# motor_line.net
KiCad netlist of a schematic drawn in EAGLE
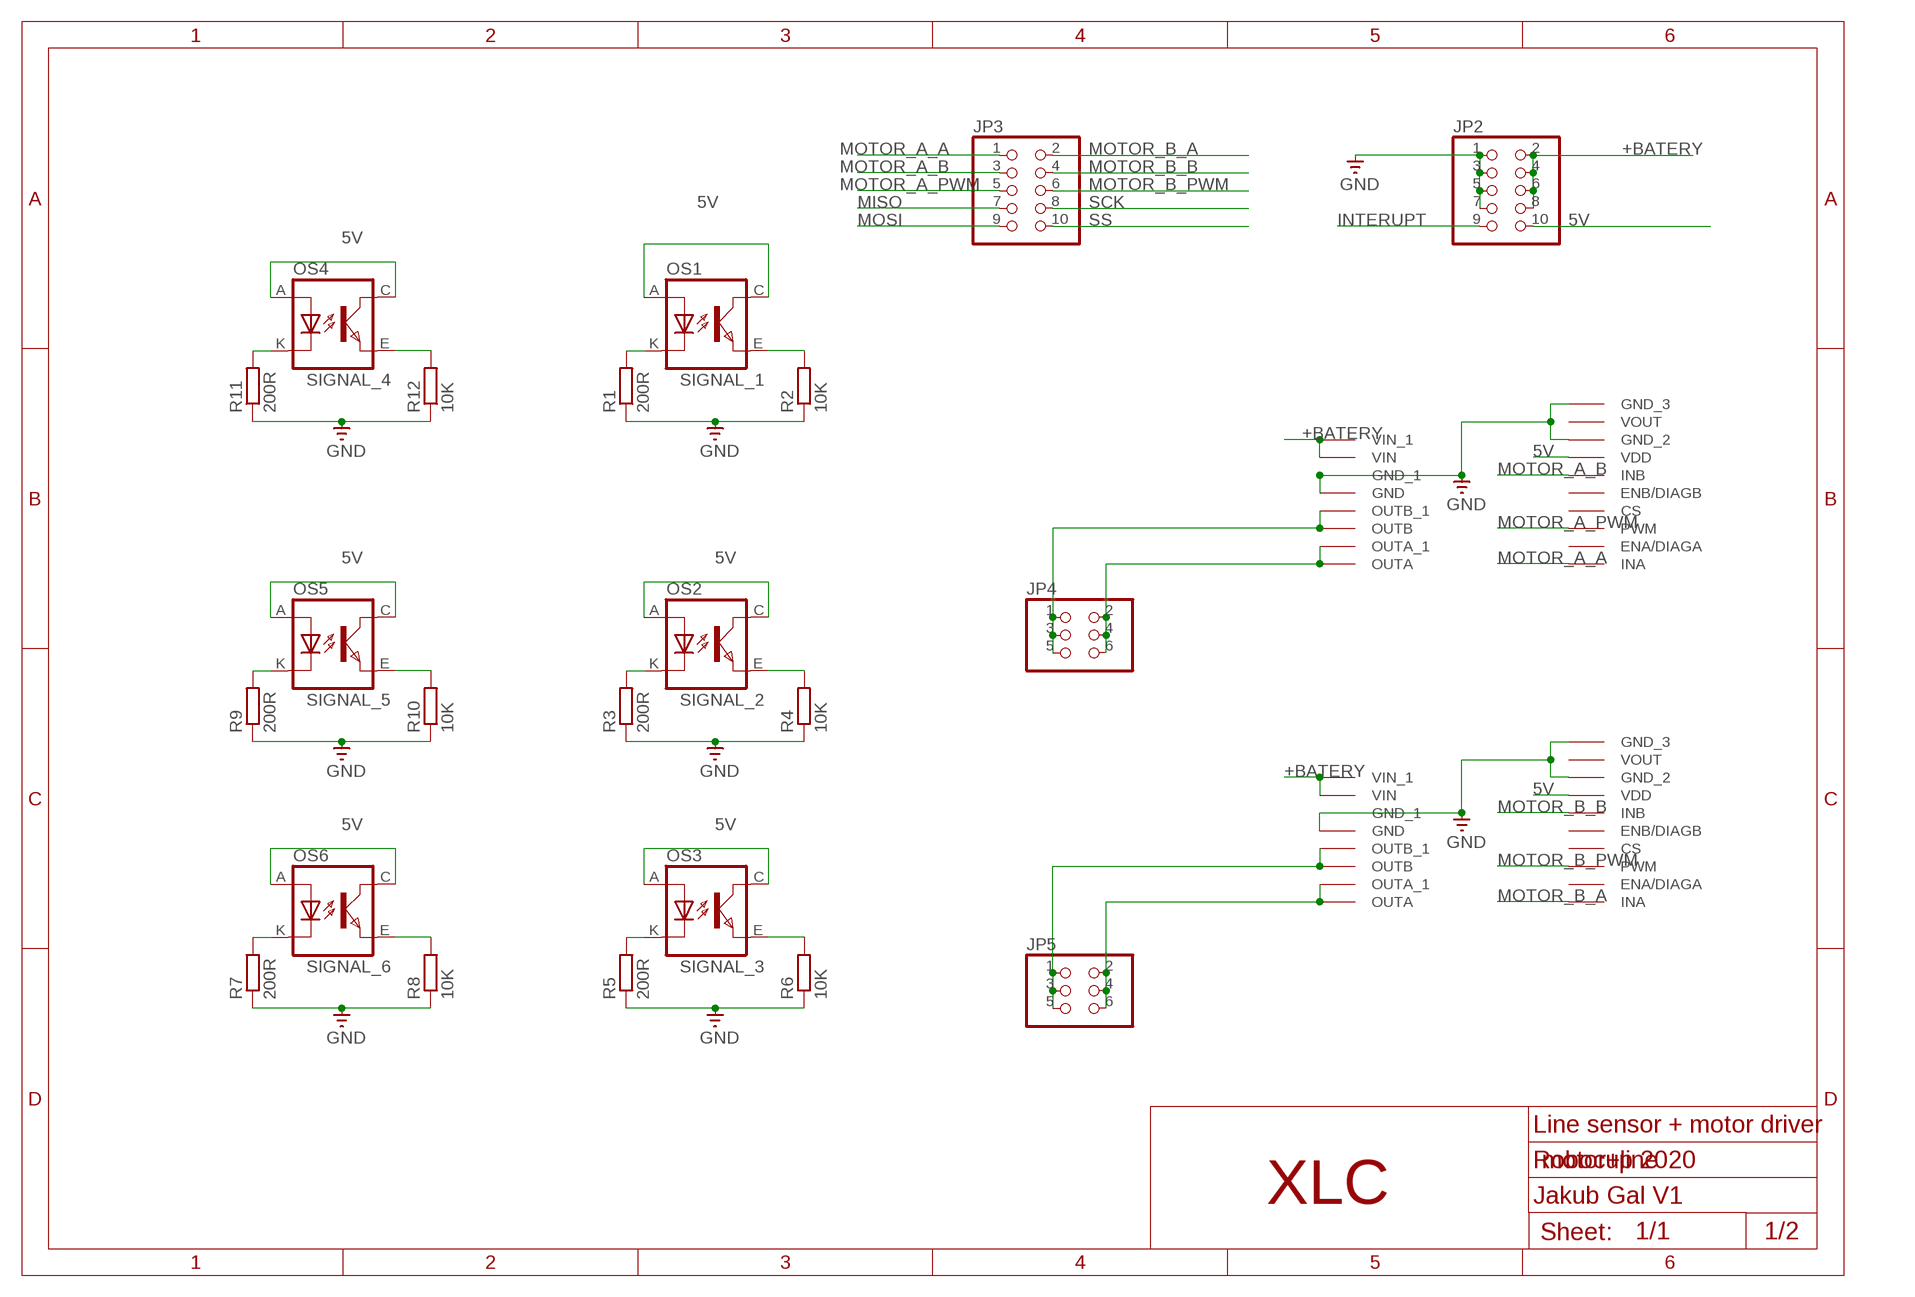
[diagram p0: schematic, sheet 1, part 1 of 2]
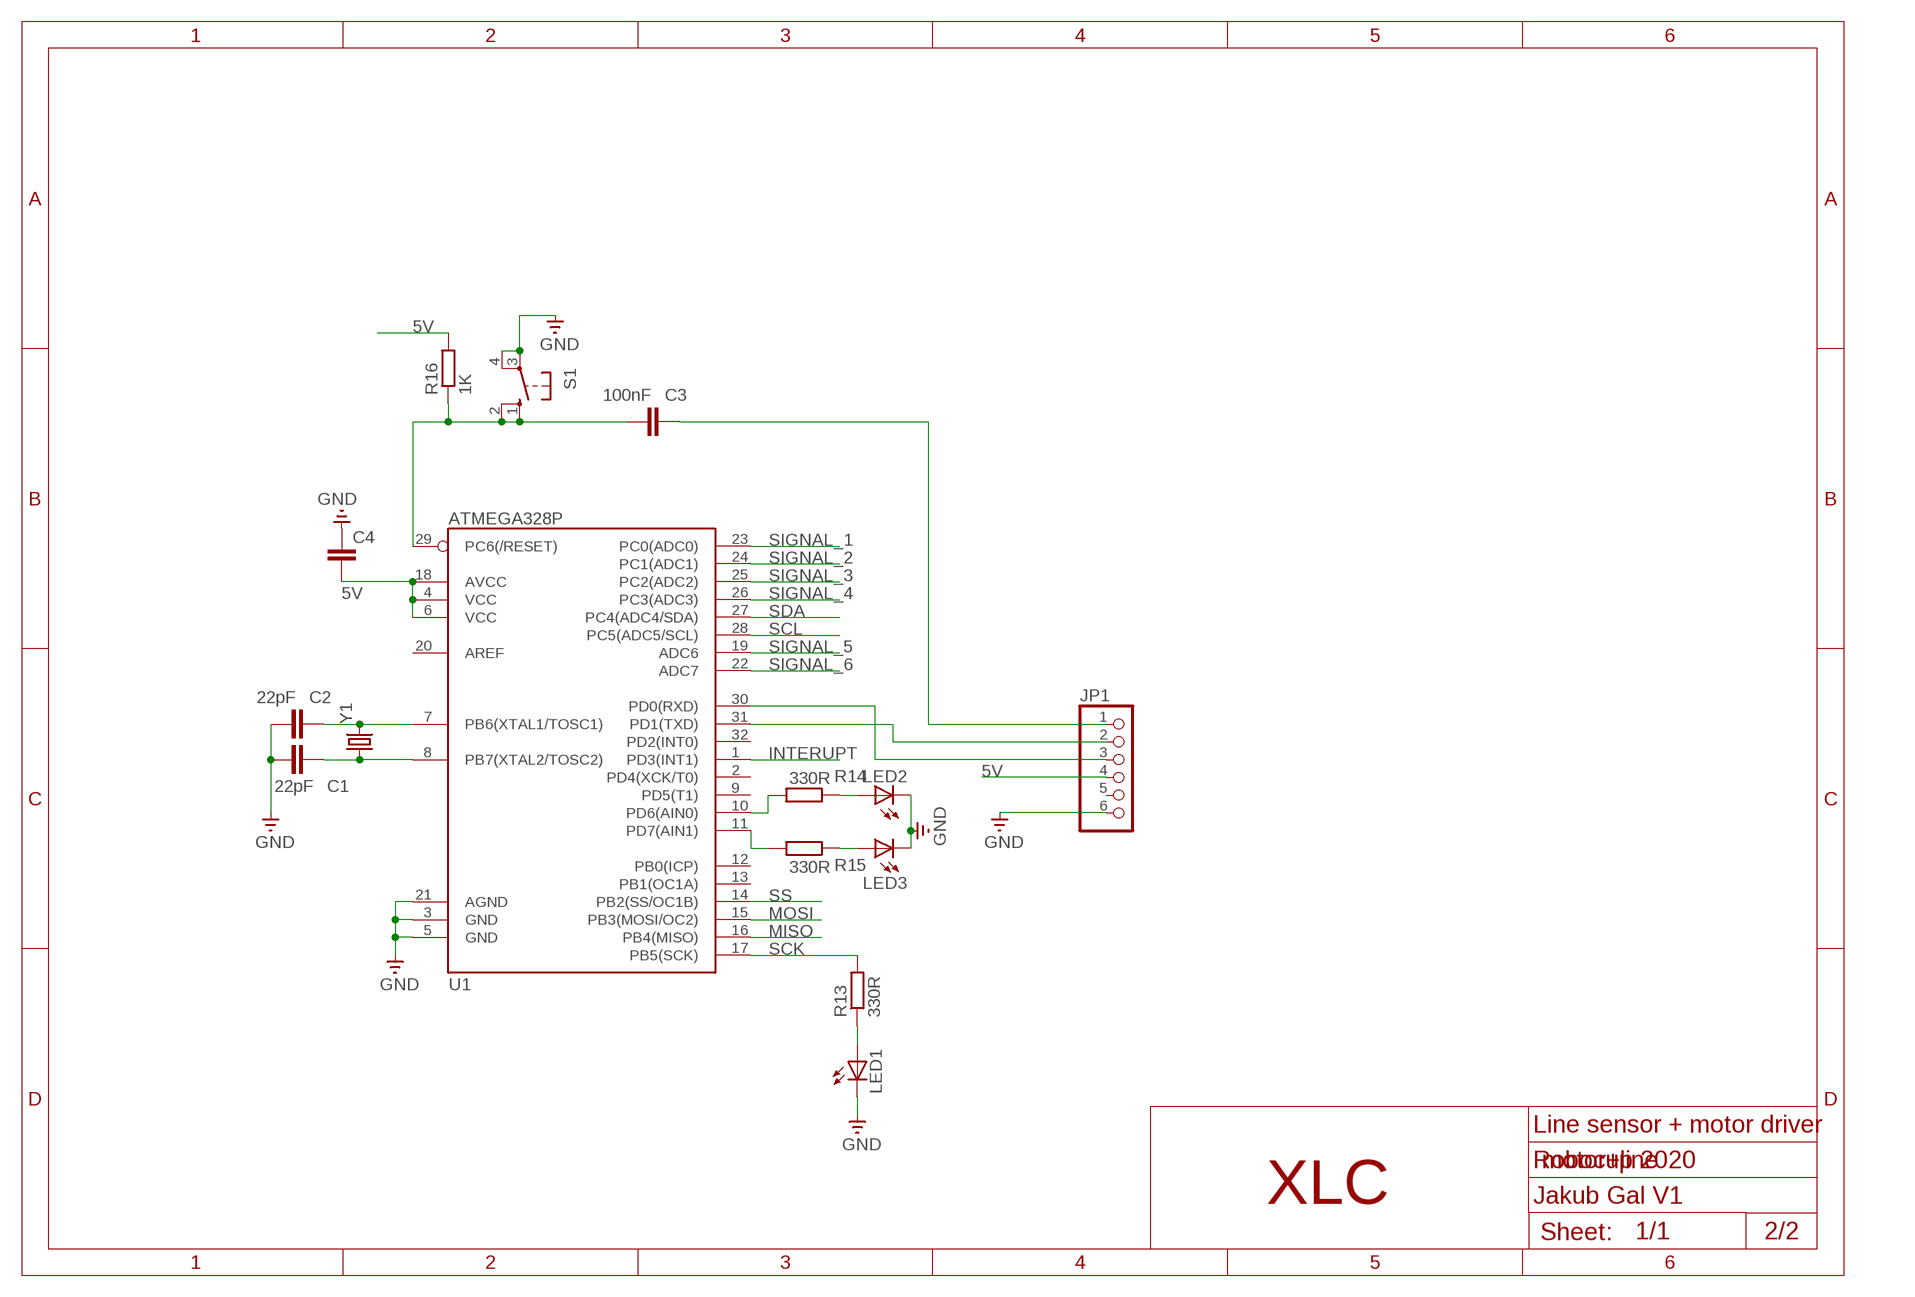
[diagram p1: schematic, sheet 1, part 2 of 2]

(export (version "E")
  (design (tool "Eeschema 10.0.6"))
  (components
    (comp (ref "C1")
      (value "22pF")
      (footprint "eagle-import:C0603")
      (libsource (lib "eagle-import") (part "C-EUC0603"))
    )
    (comp (ref "C2")
      (value "22pF")
      (footprint "eagle-import:C0603")
      (libsource (lib "eagle-import") (part "C-EUC0603"))
    )
    (comp (ref "C3")
      (value "100nF")
      (footprint "eagle-import:C0603")
      (libsource (lib "eagle-import") (part "C-EUC0603"))
    )
    (comp (ref "C4")
      (value "C-EUC0603")
      (footprint "eagle-import:C0603")
      (libsource (lib "eagle-import") (part "rcl_334_C-EUC0603"))
    )
    (comp (ref "JP1")
      (value "PINHD-1X6/90")
      (footprint "eagle-import:1X06_90")
      (libsource (lib "eagle-import") (part "PINHD-1X6/90"))
    )
    (comp (ref "JP2")
      (value "PINHD-2X5")
      (footprint "eagle-import:2X05")
      (libsource (lib "eagle-import") (part "PINHD-2X5"))
    )
    (comp (ref "JP3")
      (value "PINHD-2X5")
      (footprint "eagle-import:2X05")
      (libsource (lib "eagle-import") (part "PINHD-2X5"))
    )
    (comp (ref "JP4")
      (value "PINHD-2X3")
      (footprint "eagle-import:2X03")
      (libsource (lib "eagle-import") (part "PINHD-2X3"))
    )
    (comp (ref "JP5")
      (value "PINHD-2X3")
      (footprint "eagle-import:2X03")
      (libsource (lib "eagle-import") (part "PINHD-2X3"))
    )
    (comp (ref "LED1")
      (value "LEDCHIPLED_0603")
      (footprint "eagle-import:CHIPLED_0603")
      (libsource (lib "eagle-import") (part "LEDCHIPLED_0603"))
    )
    (comp (ref "LED2")
      (value "LEDCHIPLED_0603")
      (footprint "eagle-import:CHIPLED_0603")
      (libsource (lib "eagle-import") (part "LEDCHIPLED_0603"))
    )
    (comp (ref "LED3")
      (value "LEDCHIPLED_0603")
      (footprint "eagle-import:CHIPLED_0603")
      (libsource (lib "eagle-import") (part "LEDCHIPLED_0603"))
    )
    (comp (ref "OS1")
      (value "TCRT5000")
      (footprint "eagle-import:TCRT5000")
      (libsource (lib "eagle-import") (part "TCRT5000"))
    )
    (comp (ref "OS2")
      (value "TCRT5000")
      (footprint "eagle-import:TCRT5000")
      (libsource (lib "eagle-import") (part "TCRT5000"))
    )
    (comp (ref "OS3")
      (value "TCRT5000")
      (footprint "eagle-import:TCRT5000")
      (libsource (lib "eagle-import") (part "TCRT5000"))
    )
    (comp (ref "OS4")
      (value "TCRT5000")
      (footprint "eagle-import:TCRT5000")
      (fields (field (name "SPICEPREFIX") "O"))
      (libsource (lib "eagle-import") (part "TCRT5000"))
    )
    (comp (ref "OS5")
      (value "TCRT5000")
      (footprint "eagle-import:TCRT5000")
      (libsource (lib "eagle-import") (part "TCRT5000"))
    )
    (comp (ref "OS6")
      (value "TCRT5000")
      (footprint "eagle-import:TCRT5000")
      (fields (field (name "SPICEPREFIX") "O"))
      (libsource (lib "eagle-import") (part "TCRT5000"))
    )
    (comp (ref "R1")
      (value "200R")
      (footprint "eagle-import:R0603")
      (libsource (lib "eagle-import") (part "R-EU_R0603"))
    )
    (comp (ref "R2")
      (value "10K")
      (footprint "eagle-import:R0603")
      (libsource (lib "eagle-import") (part "R-EU_R0603"))
    )
    (comp (ref "R3")
      (value "200R")
      (footprint "eagle-import:R0603")
      (libsource (lib "eagle-import") (part "R-EU_R0603"))
    )
    (comp (ref "R4")
      (value "10K")
      (footprint "eagle-import:R0603")
      (libsource (lib "eagle-import") (part "R-EU_R0603"))
    )
    (comp (ref "R5")
      (value "200R")
      (footprint "eagle-import:R0603")
      (libsource (lib "eagle-import") (part "R-EU_R0603"))
    )
    (comp (ref "R6")
      (value "10K")
      (footprint "eagle-import:R0603")
      (libsource (lib "eagle-import") (part "R-EU_R0603"))
    )
    (comp (ref "R7")
      (value "200R")
      (footprint "eagle-import:R0603")
      (libsource (lib "eagle-import") (part "R-EU_R0603"))
    )
    (comp (ref "R8")
      (value "10K")
      (footprint "eagle-import:R0603")
      (libsource (lib "eagle-import") (part "R-EU_R0603"))
    )
    (comp (ref "R9")
      (value "200R")
      (footprint "eagle-import:R0603")
      (libsource (lib "eagle-import") (part "R-EU_R0603"))
    )
    (comp (ref "R10")
      (value "10K")
      (footprint "eagle-import:R0603")
      (libsource (lib "eagle-import") (part "R-EU_R0603"))
    )
    (comp (ref "R11")
      (value "200R")
      (footprint "eagle-import:R0603")
      (libsource (lib "eagle-import") (part "R-EU_R0603"))
    )
    (comp (ref "R12")
      (value "10K")
      (footprint "eagle-import:R0603")
      (libsource (lib "eagle-import") (part "R-EU_R0603"))
    )
    (comp (ref "R13")
      (value "330R")
      (footprint "eagle-import:R0603")
      (libsource (lib "eagle-import") (part "R-EU_R0603"))
    )
    (comp (ref "R14")
      (value "330R")
      (footprint "eagle-import:R0603")
      (libsource (lib "eagle-import") (part "R-EU_R0603"))
    )
    (comp (ref "R15")
      (value "330R")
      (footprint "eagle-import:R0603")
      (libsource (lib "eagle-import") (part "R-EU_R0603"))
    )
    (comp (ref "R16")
      (value "1K")
      (footprint "eagle-import:R0603")
      (libsource (lib "eagle-import") (part "R-EU_R0603"))
    )
    (comp (ref "S1")
      (value "10-XX")
      (footprint "eagle-import:B3F-10XX")
      (fields (field (name "MPN") "B3F-1000"))
      (libsource (lib "eagle-import") (part "10-XX"))
    )
    (comp (ref "U$1")
      (value "MOTOR_DRIVER")
      (footprint "eagle-import:MOTOR_DRIVER")
      (libsource (lib "eagle-import") (part "MOTOR_DRIVER"))
    )
    (comp (ref "U$2")
      (value "MOTOR_DRIVER")
      (footprint "eagle-import:MOTOR_DRIVER")
      (libsource (lib "eagle-import") (part "MOTOR_DRIVER"))
    )
    (comp (ref "U1")
      (value "ATMEGA328P")
      (footprint "eagle-import:TQFP32-08")
      (libsource (lib "eagle-import") (part "ATMEGA328_SMT"))
    )
    (comp (ref "Y1")
      (value "CRYSTALHC49US")
      (footprint "eagle-import:HC49US")
      (libsource (lib "eagle-import") (part "CRYSTALHC49US"))
    )
  )
  (nets
    (net (code "1") (name "/+BATERY") (class "Default")
      (node (ref "JP2") (pin "2") (pinfunction "2_2") (pintype "passive"))
      (node (ref "JP2") (pin "4") (pinfunction "4_4") (pintype "passive"))
      (node (ref "JP2") (pin "6") (pinfunction "6_6") (pintype "passive"))
      (node (ref "JP2") (pin "8") (pinfunction "8_8") (pintype "passive"))
      (node (ref "U$1") (pin "VIN") (pinfunction "VIN_VIN") (pintype "bidirectional"))
      (node (ref "U$1") (pin "VIN_1") (pinfunction "VIN_1_VIN_1") (pintype "bidirectional"))
      (node (ref "U$2") (pin "VIN") (pinfunction "VIN_VIN") (pintype "bidirectional"))
      (node (ref "U$2") (pin "VIN_1") (pinfunction "VIN_1_VIN_1") (pintype "bidirectional"))
    )
    (net (code "2") (name "/5V") (class "Default")
      (node (ref "C4") (pin "2") (pinfunction "2_2") (pintype "passive"))
      (node (ref "JP1") (pin "4") (pinfunction "4_4") (pintype "passive"))
      (node (ref "JP2") (pin "10") (pinfunction "10_10") (pintype "passive"))
      (node (ref "OS1") (pin "A") (pinfunction "ANODE_A") (pintype "passive"))
      (node (ref "OS1") (pin "C") (pinfunction "COLLECTOR_C") (pintype "passive"))
      (node (ref "OS2") (pin "A") (pinfunction "ANODE_A") (pintype "passive"))
      (node (ref "OS2") (pin "C") (pinfunction "COLLECTOR_C") (pintype "passive"))
      (node (ref "OS3") (pin "A") (pinfunction "ANODE_A") (pintype "passive"))
      (node (ref "OS3") (pin "C") (pinfunction "COLLECTOR_C") (pintype "passive"))
      (node (ref "OS4") (pin "A") (pinfunction "ANODE_A") (pintype "passive"))
      (node (ref "OS4") (pin "C") (pinfunction "COLLECTOR_C") (pintype "passive"))
      (node (ref "OS5") (pin "A") (pinfunction "ANODE_A") (pintype "passive"))
      (node (ref "OS5") (pin "C") (pinfunction "COLLECTOR_C") (pintype "passive"))
      (node (ref "OS6") (pin "A") (pinfunction "ANODE_A") (pintype "passive"))
      (node (ref "OS6") (pin "C") (pinfunction "COLLECTOR_C") (pintype "passive"))
      (node (ref "R16") (pin "2") (pinfunction "2_2") (pintype "passive"))
      (node (ref "U$1") (pin "VDD") (pinfunction "VDD_VDD") (pintype "bidirectional"))
      (node (ref "U$2") (pin "VDD") (pinfunction "VDD_VDD") (pintype "bidirectional"))
      (node (ref "U1") (pin "18") (pinfunction "AVCC_18") (pintype "bidirectional"))
      (node (ref "U1") (pin "4") (pinfunction "VCC_4") (pintype "bidirectional"))
      (node (ref "U1") (pin "6") (pinfunction "VCC_6") (pintype "bidirectional"))
    )
    (net (code "3") (name "/INTERUPT") (class "Default")
      (node (ref "JP2") (pin "9") (pinfunction "9_9") (pintype "passive"))
      (node (ref "U1") (pin "1") (pinfunction "PD3(INT1)_1") (pintype "bidirectional"))
    )
    (net (code "4") (name "/MISO") (class "Default")
      (node (ref "JP3") (pin "7") (pinfunction "7_7") (pintype "passive"))
      (node (ref "U1") (pin "16") (pinfunction "PB4(MISO)_16") (pintype "bidirectional"))
    )
    (net (code "5") (name "/MOSI") (class "Default")
      (node (ref "JP3") (pin "9") (pinfunction "9_9") (pintype "passive"))
      (node (ref "U1") (pin "15") (pinfunction "PB3(MOSI/OC2)_15") (pintype "bidirectional"))
    )
    (net (code "6") (name "/MOTOR_A_A") (class "Default")
      (node (ref "JP3") (pin "1") (pinfunction "1_1") (pintype "passive"))
      (node (ref "U$1") (pin "INA") (pinfunction "INA_INA") (pintype "bidirectional"))
    )
    (net (code "7") (name "/MOTOR_A_B") (class "Default")
      (node (ref "JP3") (pin "3") (pinfunction "3_3") (pintype "passive"))
      (node (ref "U$1") (pin "INB") (pinfunction "INB_INB") (pintype "bidirectional"))
    )
    (net (code "8") (name "/MOTOR_A_PWM") (class "Default")
      (node (ref "JP3") (pin "5") (pinfunction "5_5") (pintype "passive"))
      (node (ref "U$1") (pin "PWM") (pinfunction "PWM_PWM") (pintype "bidirectional"))
    )
    (net (code "9") (name "/MOTOR_B_A") (class "Default")
      (node (ref "JP3") (pin "2") (pinfunction "2_2") (pintype "passive"))
      (node (ref "U$2") (pin "INA") (pinfunction "INA_INA") (pintype "bidirectional"))
    )
    (net (code "10") (name "/MOTOR_B_B") (class "Default")
      (node (ref "JP3") (pin "4") (pinfunction "4_4") (pintype "passive"))
      (node (ref "U$2") (pin "INB") (pinfunction "INB_INB") (pintype "bidirectional"))
    )
    (net (code "11") (name "/MOTOR_B_PWM") (class "Default")
      (node (ref "JP3") (pin "6") (pinfunction "6_6") (pintype "passive"))
      (node (ref "U$2") (pin "PWM") (pinfunction "PWM_PWM") (pintype "bidirectional"))
    )
    (net (code "12") (name "/SCK") (class "Default")
      (node (ref "JP3") (pin "8") (pinfunction "8_8") (pintype "passive"))
      (node (ref "R13") (pin "2") (pinfunction "2_2") (pintype "passive"))
      (node (ref "U1") (pin "17") (pinfunction "PB5(SCK)_17") (pintype "bidirectional"))
    )
    (net (code "13") (name "/SCL") (class "Default")
      (node (ref "U1") (pin "28") (pinfunction "PC5(ADC5/SCL)_28") (pintype "bidirectional"))
    )
    (net (code "14") (name "/SDA") (class "Default")
      (node (ref "U1") (pin "27") (pinfunction "PC4(ADC4/SDA)_27") (pintype "bidirectional"))
    )
    (net (code "15") (name "/SIGNAL_1") (class "Default")
      (node (ref "OS1") (pin "E") (pinfunction "EMITTER_E") (pintype "passive"))
      (node (ref "R2") (pin "2") (pinfunction "2_2") (pintype "passive"))
      (node (ref "U1") (pin "23") (pinfunction "PC0(ADC0)_23") (pintype "bidirectional"))
    )
    (net (code "16") (name "/SIGNAL_2") (class "Default")
      (node (ref "OS2") (pin "E") (pinfunction "EMITTER_E") (pintype "passive"))
      (node (ref "R4") (pin "2") (pinfunction "2_2") (pintype "passive"))
      (node (ref "U1") (pin "24") (pinfunction "PC1(ADC1)_24") (pintype "bidirectional"))
    )
    (net (code "17") (name "/SIGNAL_3") (class "Default")
      (node (ref "OS3") (pin "E") (pinfunction "EMITTER_E") (pintype "passive"))
      (node (ref "R6") (pin "2") (pinfunction "2_2") (pintype "passive"))
      (node (ref "U1") (pin "25") (pinfunction "PC2(ADC2)_25") (pintype "bidirectional"))
    )
    (net (code "18") (name "/SIGNAL_4") (class "Default")
      (node (ref "OS4") (pin "E") (pinfunction "EMITTER_E") (pintype "passive"))
      (node (ref "R12") (pin "2") (pinfunction "2_2") (pintype "passive"))
      (node (ref "U1") (pin "26") (pinfunction "PC3(ADC3)_26") (pintype "bidirectional"))
    )
    (net (code "19") (name "/SIGNAL_5") (class "Default")
      (node (ref "OS5") (pin "E") (pinfunction "EMITTER_E") (pintype "passive"))
      (node (ref "R10") (pin "2") (pinfunction "2_2") (pintype "passive"))
      (node (ref "U1") (pin "19") (pinfunction "ADC6_19") (pintype "bidirectional"))
    )
    (net (code "20") (name "/SIGNAL_6") (class "Default")
      (node (ref "OS6") (pin "E") (pinfunction "EMITTER_E") (pintype "passive"))
      (node (ref "R8") (pin "2") (pinfunction "2_2") (pintype "passive"))
      (node (ref "U1") (pin "22") (pinfunction "ADC7_22") (pintype "bidirectional"))
    )
    (net (code "21") (name "/SS") (class "Default")
      (node (ref "JP3") (pin "10") (pinfunction "10_10") (pintype "passive"))
      (node (ref "U1") (pin "14") (pinfunction "PB2(SS/OC1B)_14") (pintype "bidirectional"))
    )
    (net (code "22") (name "GND") (class "Default")
      (node (ref "C1") (pin "1") (pinfunction "1_1") (pintype "passive"))
      (node (ref "C2") (pin "1") (pinfunction "1_1") (pintype "passive"))
      (node (ref "C4") (pin "1") (pinfunction "1_1") (pintype "passive"))
      (node (ref "JP1") (pin "6") (pinfunction "6_6") (pintype "passive"))
      (node (ref "JP2") (pin "1") (pinfunction "1_1") (pintype "passive"))
      (node (ref "JP2") (pin "3") (pinfunction "3_3") (pintype "passive"))
      (node (ref "JP2") (pin "5") (pinfunction "5_5") (pintype "passive"))
      (node (ref "JP2") (pin "7") (pinfunction "7_7") (pintype "passive"))
      (node (ref "LED1") (pin "C") (pinfunction "C_C") (pintype "passive"))
      (node (ref "LED2") (pin "C") (pinfunction "C_C") (pintype "passive"))
      (node (ref "LED3") (pin "C") (pinfunction "C_C") (pintype "passive"))
      (node (ref "R1") (pin "1") (pinfunction "1_1") (pintype "passive"))
      (node (ref "R10") (pin "1") (pinfunction "1_1") (pintype "passive"))
      (node (ref "R11") (pin "1") (pinfunction "1_1") (pintype "passive"))
      (node (ref "R12") (pin "1") (pinfunction "1_1") (pintype "passive"))
      (node (ref "R2") (pin "1") (pinfunction "1_1") (pintype "passive"))
      (node (ref "R3") (pin "1") (pinfunction "1_1") (pintype "passive"))
      (node (ref "R4") (pin "1") (pinfunction "1_1") (pintype "passive"))
      (node (ref "R5") (pin "1") (pinfunction "1_1") (pintype "passive"))
      (node (ref "R6") (pin "1") (pinfunction "1_1") (pintype "passive"))
      (node (ref "R7") (pin "1") (pinfunction "1_1") (pintype "passive"))
      (node (ref "R8") (pin "1") (pinfunction "1_1") (pintype "passive"))
      (node (ref "R9") (pin "1") (pinfunction "1_1") (pintype "passive"))
      (node (ref "S1") (pin "3") (pinfunction "P_3") (pintype "passive"))
      (node (ref "S1") (pin "4") (pinfunction "P1_4") (pintype "passive"))
      (node (ref "U$1") (pin "GND") (pinfunction "GND_GND") (pintype "bidirectional"))
      (node (ref "U$1") (pin "GND_1") (pinfunction "GND_1_GND_1") (pintype "bidirectional"))
      (node (ref "U$1") (pin "GND_2") (pinfunction "GND_2_GND_2") (pintype "bidirectional"))
      (node (ref "U$1") (pin "GND_3") (pinfunction "GND_3_GND_3") (pintype "bidirectional"))
      (node (ref "U$2") (pin "GND") (pinfunction "GND_GND") (pintype "bidirectional"))
      (node (ref "U$2") (pin "GND_1") (pinfunction "GND_1_GND_1") (pintype "bidirectional"))
      (node (ref "U$2") (pin "GND_2") (pinfunction "GND_2_GND_2") (pintype "bidirectional"))
      (node (ref "U$2") (pin "GND_3") (pinfunction "GND_3_GND_3") (pintype "bidirectional"))
      (node (ref "U1") (pin "21") (pinfunction "AGND_21") (pintype "bidirectional"))
      (node (ref "U1") (pin "3") (pinfunction "GND_3") (pintype "bidirectional"))
      (node (ref "U1") (pin "5") (pinfunction "GND_5") (pintype "bidirectional"))
    )
    (net (code "23") (name "Net-(C3-Pad2)") (class "Default")
      (node (ref "C3") (pin "2") (pinfunction "2_2") (pintype "passive"))
      (node (ref "JP1") (pin "1") (pinfunction "1_1") (pintype "passive"))
    )
    (net (code "24") (name "Net-(JP4-Pad1)") (class "Default")
      (node (ref "JP4") (pin "1") (pinfunction "1_1") (pintype "passive"))
      (node (ref "JP4") (pin "3") (pinfunction "3_3") (pintype "passive"))
      (node (ref "JP4") (pin "5") (pinfunction "5_5") (pintype "passive"))
      (node (ref "U$1") (pin "OUTB") (pinfunction "OUTB_OUTB") (pintype "bidirectional"))
      (node (ref "U$1") (pin "OUTB_1") (pinfunction "OUTB_1_OUTB_1") (pintype "bidirectional"))
    )
    (net (code "25") (name "Net-(JP4-Pad2)") (class "Default")
      (node (ref "JP4") (pin "2") (pinfunction "2_2") (pintype "passive"))
      (node (ref "JP4") (pin "4") (pinfunction "4_4") (pintype "passive"))
      (node (ref "JP4") (pin "6") (pinfunction "6_6") (pintype "passive"))
      (node (ref "U$1") (pin "OUTA") (pinfunction "OUTA_OUTA") (pintype "bidirectional"))
      (node (ref "U$1") (pin "OUTA_1") (pinfunction "OUTA_1_OUTA_1") (pintype "bidirectional"))
    )
    (net (code "26") (name "Net-(JP5-Pad1)") (class "Default")
      (node (ref "JP5") (pin "1") (pinfunction "1_1") (pintype "passive"))
      (node (ref "JP5") (pin "3") (pinfunction "3_3") (pintype "passive"))
      (node (ref "JP5") (pin "5") (pinfunction "5_5") (pintype "passive"))
      (node (ref "U$2") (pin "OUTB") (pinfunction "OUTB_OUTB") (pintype "bidirectional"))
      (node (ref "U$2") (pin "OUTB_1") (pinfunction "OUTB_1_OUTB_1") (pintype "bidirectional"))
    )
    (net (code "27") (name "Net-(JP5-Pad2)") (class "Default")
      (node (ref "JP5") (pin "2") (pinfunction "2_2") (pintype "passive"))
      (node (ref "JP5") (pin "4") (pinfunction "4_4") (pintype "passive"))
      (node (ref "JP5") (pin "6") (pinfunction "6_6") (pintype "passive"))
      (node (ref "U$2") (pin "OUTA") (pinfunction "OUTA_OUTA") (pintype "bidirectional"))
      (node (ref "U$2") (pin "OUTA_1") (pinfunction "OUTA_1_OUTA_1") (pintype "bidirectional"))
    )
    (net (code "28") (name "Net-(LED1-PadA)") (class "Default")
      (node (ref "LED1") (pin "A") (pinfunction "A_A") (pintype "passive"))
      (node (ref "R13") (pin "1") (pinfunction "1_1") (pintype "passive"))
    )
    (net (code "29") (name "Net-(LED2-PadA)") (class "Default")
      (node (ref "LED2") (pin "A") (pinfunction "A_A") (pintype "passive"))
      (node (ref "R14") (pin "1") (pinfunction "1_1") (pintype "passive"))
    )
    (net (code "30") (name "Net-(LED3-PadA)") (class "Default")
      (node (ref "LED3") (pin "A") (pinfunction "A_A") (pintype "passive"))
      (node (ref "R15") (pin "1") (pinfunction "1_1") (pintype "passive"))
    )
    (net (code "31") (name "Net-(OS1-CATHODE)") (class "Default")
      (node (ref "OS1") (pin "K") (pinfunction "CATHODE_K") (pintype "passive"))
      (node (ref "R1") (pin "2") (pinfunction "2_2") (pintype "passive"))
    )
    (net (code "32") (name "Net-(OS2-CATHODE)") (class "Default")
      (node (ref "OS2") (pin "K") (pinfunction "CATHODE_K") (pintype "passive"))
      (node (ref "R3") (pin "2") (pinfunction "2_2") (pintype "passive"))
    )
    (net (code "33") (name "Net-(OS3-CATHODE)") (class "Default")
      (node (ref "OS3") (pin "K") (pinfunction "CATHODE_K") (pintype "passive"))
      (node (ref "R5") (pin "2") (pinfunction "2_2") (pintype "passive"))
    )
    (net (code "34") (name "Net-(OS4-CATHODE)") (class "Default")
      (node (ref "OS4") (pin "K") (pinfunction "CATHODE_K") (pintype "passive"))
      (node (ref "R11") (pin "2") (pinfunction "2_2") (pintype "passive"))
    )
    (net (code "35") (name "Net-(OS5-CATHODE)") (class "Default")
      (node (ref "OS5") (pin "K") (pinfunction "CATHODE_K") (pintype "passive"))
      (node (ref "R9") (pin "2") (pinfunction "2_2") (pintype "passive"))
    )
    (net (code "36") (name "Net-(OS6-CATHODE)") (class "Default")
      (node (ref "OS6") (pin "K") (pinfunction "CATHODE_K") (pintype "passive"))
      (node (ref "R7") (pin "2") (pinfunction "2_2") (pintype "passive"))
    )
    (net (code "37") (name "Net-(S1-S)") (class "Default")
      (node (ref "C3") (pin "1") (pinfunction "1_1") (pintype "passive"))
      (node (ref "R16") (pin "1") (pinfunction "1_1") (pintype "passive"))
      (node (ref "S1") (pin "1") (pinfunction "S_1") (pintype "passive"))
      (node (ref "S1") (pin "2") (pinfunction "S1_2") (pintype "passive"))
      (node (ref "U1") (pin "29") (pinfunction "PC6(/RESET)_29") (pintype "bidirectional"))
    )
    (net (code "38") (name "Net-(U1-PB6(XTAL1{slash}TOSC1))") (class "Default")
      (node (ref "C2") (pin "2") (pinfunction "2_2") (pintype "passive"))
      (node (ref "U1") (pin "7") (pinfunction "PB6(XTAL1/TOSC1)_7") (pintype "bidirectional"))
      (node (ref "Y1") (pin "2") (pinfunction "2_2") (pintype "passive"))
    )
    (net (code "39") (name "Net-(U1-PB7(XTAL2{slash}TOSC2))") (class "Default")
      (node (ref "C1") (pin "2") (pinfunction "2_2") (pintype "passive"))
      (node (ref "U1") (pin "8") (pinfunction "PB7(XTAL2/TOSC2)_8") (pintype "bidirectional"))
      (node (ref "Y1") (pin "1") (pinfunction "1_1") (pintype "passive"))
    )
    (net (code "40") (name "Net-(U1-PD0(RXD))") (class "Default")
      (node (ref "JP1") (pin "3") (pinfunction "3_3") (pintype "passive"))
      (node (ref "U1") (pin "30") (pinfunction "PD0(RXD)_30") (pintype "bidirectional"))
    )
    (net (code "41") (name "Net-(U1-PD1(TXD))") (class "Default")
      (node (ref "JP1") (pin "2") (pinfunction "2_2") (pintype "passive"))
      (node (ref "U1") (pin "31") (pinfunction "PD1(TXD)_31") (pintype "bidirectional"))
    )
    (net (code "42") (name "Net-(U1-PD6(AIN0))") (class "Default")
      (node (ref "R14") (pin "2") (pinfunction "2_2") (pintype "passive"))
      (node (ref "U1") (pin "10") (pinfunction "PD6(AIN0)_10") (pintype "bidirectional"))
    )
    (net (code "43") (name "Net-(U1-PD7(AIN1))") (class "Default")
      (node (ref "R15") (pin "2") (pinfunction "2_2") (pintype "passive"))
      (node (ref "U1") (pin "11") (pinfunction "PD7(AIN1)_11") (pintype "bidirectional"))
    )
    (net (code "44") (name "unconnected-(JP1-Pad5)") (class "Default")
      (node (ref "JP1") (pin "5") (pinfunction "5_5") (pintype "passive"))
    )
    (net (code "45") (name "unconnected-(U$1-PadCS)") (class "Default")
      (node (ref "U$1") (pin "CS") (pinfunction "CS_CS") (pintype "bidirectional"))
    )
    (net (code "46") (name "unconnected-(U$1-PadENA{slash}DIAGA)") (class "Default")
      (node (ref "U$1") (pin "ENA/DIAGA") (pinfunction "ENA/DIAGA_ENA/DIAGA") (pintype "bidirectional"))
    )
    (net (code "47") (name "unconnected-(U$1-PadENB{slash}DIAGB)") (class "Default")
      (node (ref "U$1") (pin "ENB/DIAGB") (pinfunction "ENB/DIAGB_ENB/DIAGB") (pintype "bidirectional"))
    )
    (net (code "48") (name "unconnected-(U$1-PadVOUT)") (class "Default")
      (node (ref "U$1") (pin "VOUT") (pinfunction "VOUT_VOUT") (pintype "bidirectional"))
    )
    (net (code "49") (name "unconnected-(U$2-PadCS)") (class "Default")
      (node (ref "U$2") (pin "CS") (pinfunction "CS_CS") (pintype "bidirectional"))
    )
    (net (code "50") (name "unconnected-(U$2-PadENA{slash}DIAGA)") (class "Default")
      (node (ref "U$2") (pin "ENA/DIAGA") (pinfunction "ENA/DIAGA_ENA/DIAGA") (pintype "bidirectional"))
    )
    (net (code "51") (name "unconnected-(U$2-PadENB{slash}DIAGB)") (class "Default")
      (node (ref "U$2") (pin "ENB/DIAGB") (pinfunction "ENB/DIAGB_ENB/DIAGB") (pintype "bidirectional"))
    )
    (net (code "52") (name "unconnected-(U$2-PadVOUT)") (class "Default")
      (node (ref "U$2") (pin "VOUT") (pinfunction "VOUT_VOUT") (pintype "bidirectional"))
    )
    (net (code "53") (name "unconnected-(U1-AREF-Pad20)") (class "Default")
      (node (ref "U1") (pin "20") (pinfunction "AREF_20") (pintype "bidirectional"))
    )
    (net (code "54") (name "unconnected-(U1-PB0(ICP)-Pad12)") (class "Default")
      (node (ref "U1") (pin "12") (pinfunction "PB0(ICP)_12") (pintype "bidirectional"))
    )
    (net (code "55") (name "unconnected-(U1-PB1(OC1A)-Pad13)") (class "Default")
      (node (ref "U1") (pin "13") (pinfunction "PB1(OC1A)_13") (pintype "bidirectional"))
    )
    (net (code "56") (name "unconnected-(U1-PD2(INT0)-Pad32)") (class "Default")
      (node (ref "U1") (pin "32") (pinfunction "PD2(INT0)_32") (pintype "bidirectional"))
    )
    (net (code "57") (name "unconnected-(U1-PD4(XCK{slash}T0)-Pad2)") (class "Default")
      (node (ref "U1") (pin "2") (pinfunction "PD4(XCK/T0)_2") (pintype "bidirectional"))
    )
    (net (code "58") (name "unconnected-(U1-PD5(T1)-Pad9)") (class "Default")
      (node (ref "U1") (pin "9") (pinfunction "PD5(T1)_9") (pintype "bidirectional"))
    )
  )
)
